# Power-Management.net
KiCad netlist of a schematic drawn in Altium Designer
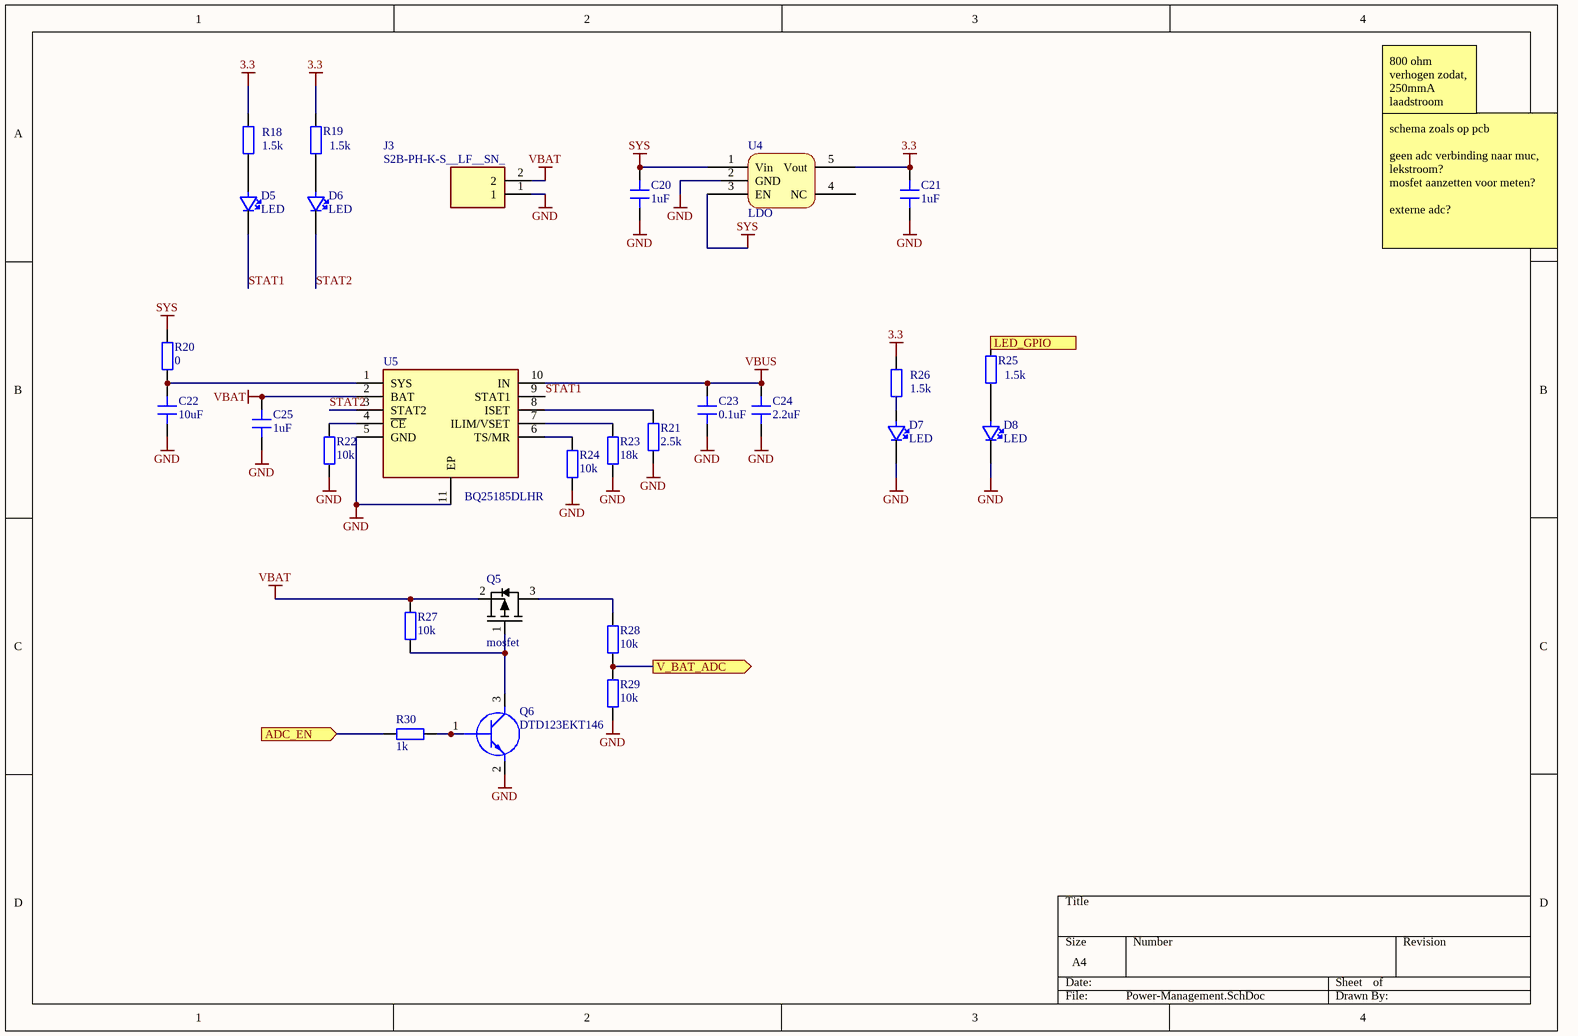
[diagram p0: Power-Management.SchDoc]

(export (version "E")
  (design (tool "Eeschema 10.0.6"))
  (components
    (comp (ref "C20") (value "1uF") (footprint "0603_CAP") (libsource (lib "passive_components") (part "C")))
    (comp (ref "C21") (value "1uF") (footprint "0603_CAP") (libsource (lib "passive_components") (part "C")))
    (comp (ref "C22") (value "10uF") (footprint "0603_CAP") (libsource (lib "passive_components") (part "C")))
    (comp (ref "C23")
      (value "0.1uF")
      (footprint "0603_CAP")
      (libsource (lib "passive_components") (part "C"))
    )
    (comp (ref "C24")
      (value "2.2uF")
      (footprint "0603_CAP")
      (libsource (lib "passive_components") (part "C"))
    )
    (comp (ref "C25") (value "1uF") (footprint "0603_CAP") (libsource (lib "passive_components") (part "C")))
    (comp (ref "D5") (value "LED") (footprint "0402_LED") (libsource (lib "passive_components") (part "LED")))
    (comp (ref "D6") (value "LED") (footprint "0402_LED") (libsource (lib "passive_components") (part "LED")))
    (comp (ref "D7") (value "LED") (footprint "0402_LED") (libsource (lib "passive_components") (part "LED")))
    (comp (ref "D8") (value "LED") (footprint "0402_LED") (libsource (lib "passive_components") (part "LED")))
    (comp (ref "J3")
      (value "S2B-PH-K-S__LF__SN_")
      (footprint "S2BPHKSLFSN")
      (description "Connector")
      (fields (field (name "MANUFACTURER_PART_NUMBER") "S2B-PH-K-S (LF)(SN)"))
      (libsource (lib "lipo_connector") (part "S2B-PH-K-S__LF__SN_"))
    )
    (comp (ref "Q5")
      (value "mosfet")
      (footprint "SOT95P230X110-3N")
      (libsource (lib "passive_components") (part "mosfet"))
    )
    (comp (ref "Q6")
      (value "DTD123EKT146")
      (footprint "FP-SS8050-G-IPC_A")
      (description "Transistor BJT NPN")
      (fields (field (name "MOUSER PART NUMBER") "755-DTD123EKT146"))
      (libsource (lib "test") (part "DTD123EKT146"))
    )
    (comp (ref "R18") (value "1.5k") (footprint "0402_RES") (libsource (lib "passive_components") (part "R")))
    (comp (ref "R19") (value "1.5k") (footprint "0402_RES") (libsource (lib "passive_components") (part "R")))
    (comp (ref "R20") (value "0") (footprint "0603") (libsource (lib "passive_components") (part "R")))
    (comp (ref "R21") (value "2.5k") (footprint "0402_RES") (libsource (lib "passive_components") (part "R")))
    (comp (ref "R22") (value "10k") (footprint "0402_RES") (libsource (lib "passive_components") (part "R")))
    (comp (ref "R23") (value "18k") (footprint "0402_RES") (libsource (lib "passive_components") (part "R")))
    (comp (ref "R24")
      (value "10k")
      (footprint "0402_RES")
      (description "NTC thermistor")
      (libsource (lib "passive_components") (part "R"))
    )
    (comp (ref "R25") (value "1.5k") (footprint "0402_RES") (libsource (lib "passive_components") (part "R")))
    (comp (ref "R26") (value "1.5k") (footprint "0402_RES") (libsource (lib "passive_components") (part "R")))
    (comp (ref "R27") (value "10k") (footprint "0402_RES") (libsource (lib "passive_components") (part "R")))
    (comp (ref "R28") (value "10k") (footprint "0402_RES") (libsource (lib "passive_components") (part "R")))
    (comp (ref "R29") (value "10k") (footprint "0402_RES") (libsource (lib "passive_components") (part "R")))
    (comp (ref "R30") (value "1k") (footprint "0402_RES") (libsource (lib "passive_components") (part "R")))
    (comp (ref "U4") (value "LDO") (footprint "LDO") (libsource (lib "passive_components") (part "LDO")))
    (comp (ref "U5")
      (value "BQ25185DLHR")
      (footprint "SON40P220X200X80-11N")
      (description "Integrated Circuit")
      (fields (field (name "MOUSER PART NUMBER") "595-BQ25185DLHR"))
      (libsource (lib "*") (part "BQ25185DLHR"))
    )
  )
  (nets
    (net (code "1") (name "/ADC_EN") (class "Default")
      (node (ref "R30") (pin "2") (pinfunction "26_2") (pintype "passive"))
    )
    (net (code "2") (name "/LED_GPIO") (class "Default")
      (node (ref "R25") (pin "2") (pinfunction "26_2") (pintype "passive"))
    )
    (net (code "3") (name "/STAT1") (class "Default")
      (node (ref "D5") (pin "2") (pinfunction "+_2") (pintype "passive"))
      (node (ref "U5") (pin "9") (pinfunction "STAT1_9") (pintype "passive"))
    )
    (net (code "4") (name "/STAT2") (class "Default")
      (node (ref "D6") (pin "2") (pinfunction "+_2") (pintype "passive"))
      (node (ref "U5") (pin "3") (pinfunction "STAT2_3") (pintype "passive"))
    )
    (net (code "5") (name "/V_BAT_ADC") (class "Default")
      (node (ref "R28") (pin "1") (pinfunction "25_1") (pintype "passive"))
      (node (ref "R29") (pin "2") (pinfunction "26_2") (pintype "passive"))
    )
    (net (code "6") (name "3.3") (class "Default")
      (node (ref "C21") (pin "2") (pinfunction "28_2") (pintype "passive"))
      (node (ref "R18") (pin "2") (pinfunction "26_2") (pintype "passive"))
      (node (ref "R19") (pin "2") (pinfunction "26_2") (pintype "passive"))
      (node (ref "R26") (pin "2") (pinfunction "26_2") (pintype "passive"))
      (node (ref "U4") (pin "5") (pinfunction "Vout_5") (pintype "passive"))
    )
    (net (code "7") (name "GND") (class "Default")
      (node (ref "C20") (pin "1") (pinfunction "1_1") (pintype "passive"))
      (node (ref "C21") (pin "1") (pinfunction "1_1") (pintype "passive"))
      (node (ref "C22") (pin "1") (pinfunction "1_1") (pintype "passive"))
      (node (ref "C23") (pin "1") (pinfunction "1_1") (pintype "passive"))
      (node (ref "C24") (pin "1") (pinfunction "1_1") (pintype "passive"))
      (node (ref "C25") (pin "1") (pinfunction "1_1") (pintype "passive"))
      (node (ref "D7") (pin "2") (pinfunction "+_2") (pintype "passive"))
      (node (ref "D8") (pin "2") (pinfunction "+_2") (pintype "passive"))
      (node (ref "J3") (pin "1") (pinfunction "1_1") (pintype "passive"))
      (node (ref "Q6") (pin "2") (pinfunction "E_2") (pintype "passive"))
      (node (ref "R21") (pin "1") (pinfunction "25_1") (pintype "passive"))
      (node (ref "R22") (pin "1") (pinfunction "25_1") (pintype "passive"))
      (node (ref "R23") (pin "1") (pinfunction "25_1") (pintype "passive"))
      (node (ref "R24") (pin "1") (pinfunction "25_1") (pintype "passive"))
      (node (ref "R29") (pin "1") (pinfunction "25_1") (pintype "passive"))
      (node (ref "U4") (pin "2") (pinfunction "GND_2") (pintype "passive"))
      (node (ref "U5") (pin "11") (pinfunction "EP_11") (pintype "passive"))
      (node (ref "U5") (pin "5") (pinfunction "GND_5") (pintype "passive"))
    )
    (net (code "8") (name "Net-(C22-28)") (class "Default")
      (node (ref "C22") (pin "2") (pinfunction "28_2") (pintype "passive"))
      (node (ref "R20") (pin "1") (pinfunction "25_1") (pintype "passive"))
      (node (ref "U5") (pin "1") (pinfunction "SYS_1") (pintype "passive"))
    )
    (net (code "9") (name "Net-(Q6-B)") (class "Default")
      (node (ref "Q6") (pin "1") (pinfunction "B_1") (pintype "passive"))
      (node (ref "R30") (pin "1") (pinfunction "25_1") (pintype "passive"))
    )
    (net (code "10") (name "Net-(Q6-C)") (class "Default")
      (node (ref "Q5") (pin "1") (pinfunction "1_1") (pintype "passive"))
      (node (ref "Q6") (pin "3") (pinfunction "C_3") (pintype "passive"))
      (node (ref "R27") (pin "1") (pinfunction "25_1") (pintype "passive"))
    )
    (net (code "11") (name "Net-(R18-25)") (class "Default")
      (node (ref "D5") (pin "1") (pinfunction "1_1") (pintype "passive"))
      (node (ref "R18") (pin "1") (pinfunction "25_1") (pintype "passive"))
    )
    (net (code "12") (name "Net-(R19-25)") (class "Default")
      (node (ref "D6") (pin "1") (pinfunction "1_1") (pintype "passive"))
      (node (ref "R19") (pin "1") (pinfunction "25_1") (pintype "passive"))
    )
    (net (code "13") (name "Net-(R21-26)") (class "Default")
      (node (ref "R21") (pin "2") (pinfunction "26_2") (pintype "passive"))
      (node (ref "U5") (pin "8") (pinfunction "ISET_8") (pintype "passive"))
    )
    (net (code "14") (name "Net-(R22-26)") (class "Default")
      (node (ref "R22") (pin "2") (pinfunction "26_2") (pintype "passive"))
      (node (ref "U5") (pin "4") (pinfunction "~{CE}_4") (pintype "passive"))
    )
    (net (code "15") (name "Net-(R23-26)") (class "Default")
      (node (ref "R23") (pin "2") (pinfunction "26_2") (pintype "passive"))
      (node (ref "U5") (pin "7") (pinfunction "ILIM/VSET_7") (pintype "passive"))
    )
    (net (code "16") (name "Net-(R24-26)") (class "Default")
      (node (ref "R24") (pin "2") (pinfunction "26_2") (pintype "passive"))
      (node (ref "U5") (pin "6") (pinfunction "TS/MR_6") (pintype "passive"))
    )
    (net (code "17") (name "Net-(R25-25)") (class "Default")
      (node (ref "D8") (pin "1") (pinfunction "1_1") (pintype "passive"))
      (node (ref "R25") (pin "1") (pinfunction "25_1") (pintype "passive"))
    )
    (net (code "18") (name "Net-(R26-25)") (class "Default")
      (node (ref "D7") (pin "1") (pinfunction "1_1") (pintype "passive"))
      (node (ref "R26") (pin "1") (pinfunction "25_1") (pintype "passive"))
    )
    (net (code "19") (name "Net-(R28-26)") (class "Default")
      (node (ref "Q5") (pin "3") (pinfunction "3_3") (pintype "passive"))
      (node (ref "R28") (pin "2") (pinfunction "26_2") (pintype "passive"))
    )
    (net (code "20") (name "SYS") (class "Default")
      (node (ref "C20") (pin "2") (pinfunction "28_2") (pintype "passive"))
      (node (ref "R20") (pin "2") (pinfunction "26_2") (pintype "passive"))
      (node (ref "U4") (pin "1") (pinfunction "Vin_1") (pintype "passive"))
      (node (ref "U4") (pin "3") (pinfunction "EN_3") (pintype "passive"))
    )
    (net (code "21") (name "VBAT") (class "Default")
      (node (ref "C25") (pin "2") (pinfunction "28_2") (pintype "passive"))
      (node (ref "J3") (pin "2") (pinfunction "2_2") (pintype "passive"))
      (node (ref "Q5") (pin "2") (pinfunction "2_2") (pintype "passive"))
      (node (ref "R27") (pin "2") (pinfunction "26_2") (pintype "passive"))
      (node (ref "U5") (pin "2") (pinfunction "BAT_2") (pintype "passive"))
    )
    (net (code "22") (name "VBUS") (class "Default")
      (node (ref "C23") (pin "2") (pinfunction "28_2") (pintype "passive"))
      (node (ref "C24") (pin "2") (pinfunction "28_2") (pintype "passive"))
      (node (ref "U5") (pin "10") (pinfunction "IN_10") (pintype "passive"))
    )
    (net (code "23") (name "unconnected-(U4-NC-Pad4)") (class "Default")
      (node (ref "U4") (pin "4") (pinfunction "NC_4") (pintype "passive"))
    )
  )
)
